# AliCampoPesca.net
KiCad netlist of a schematic drawn in EAGLE
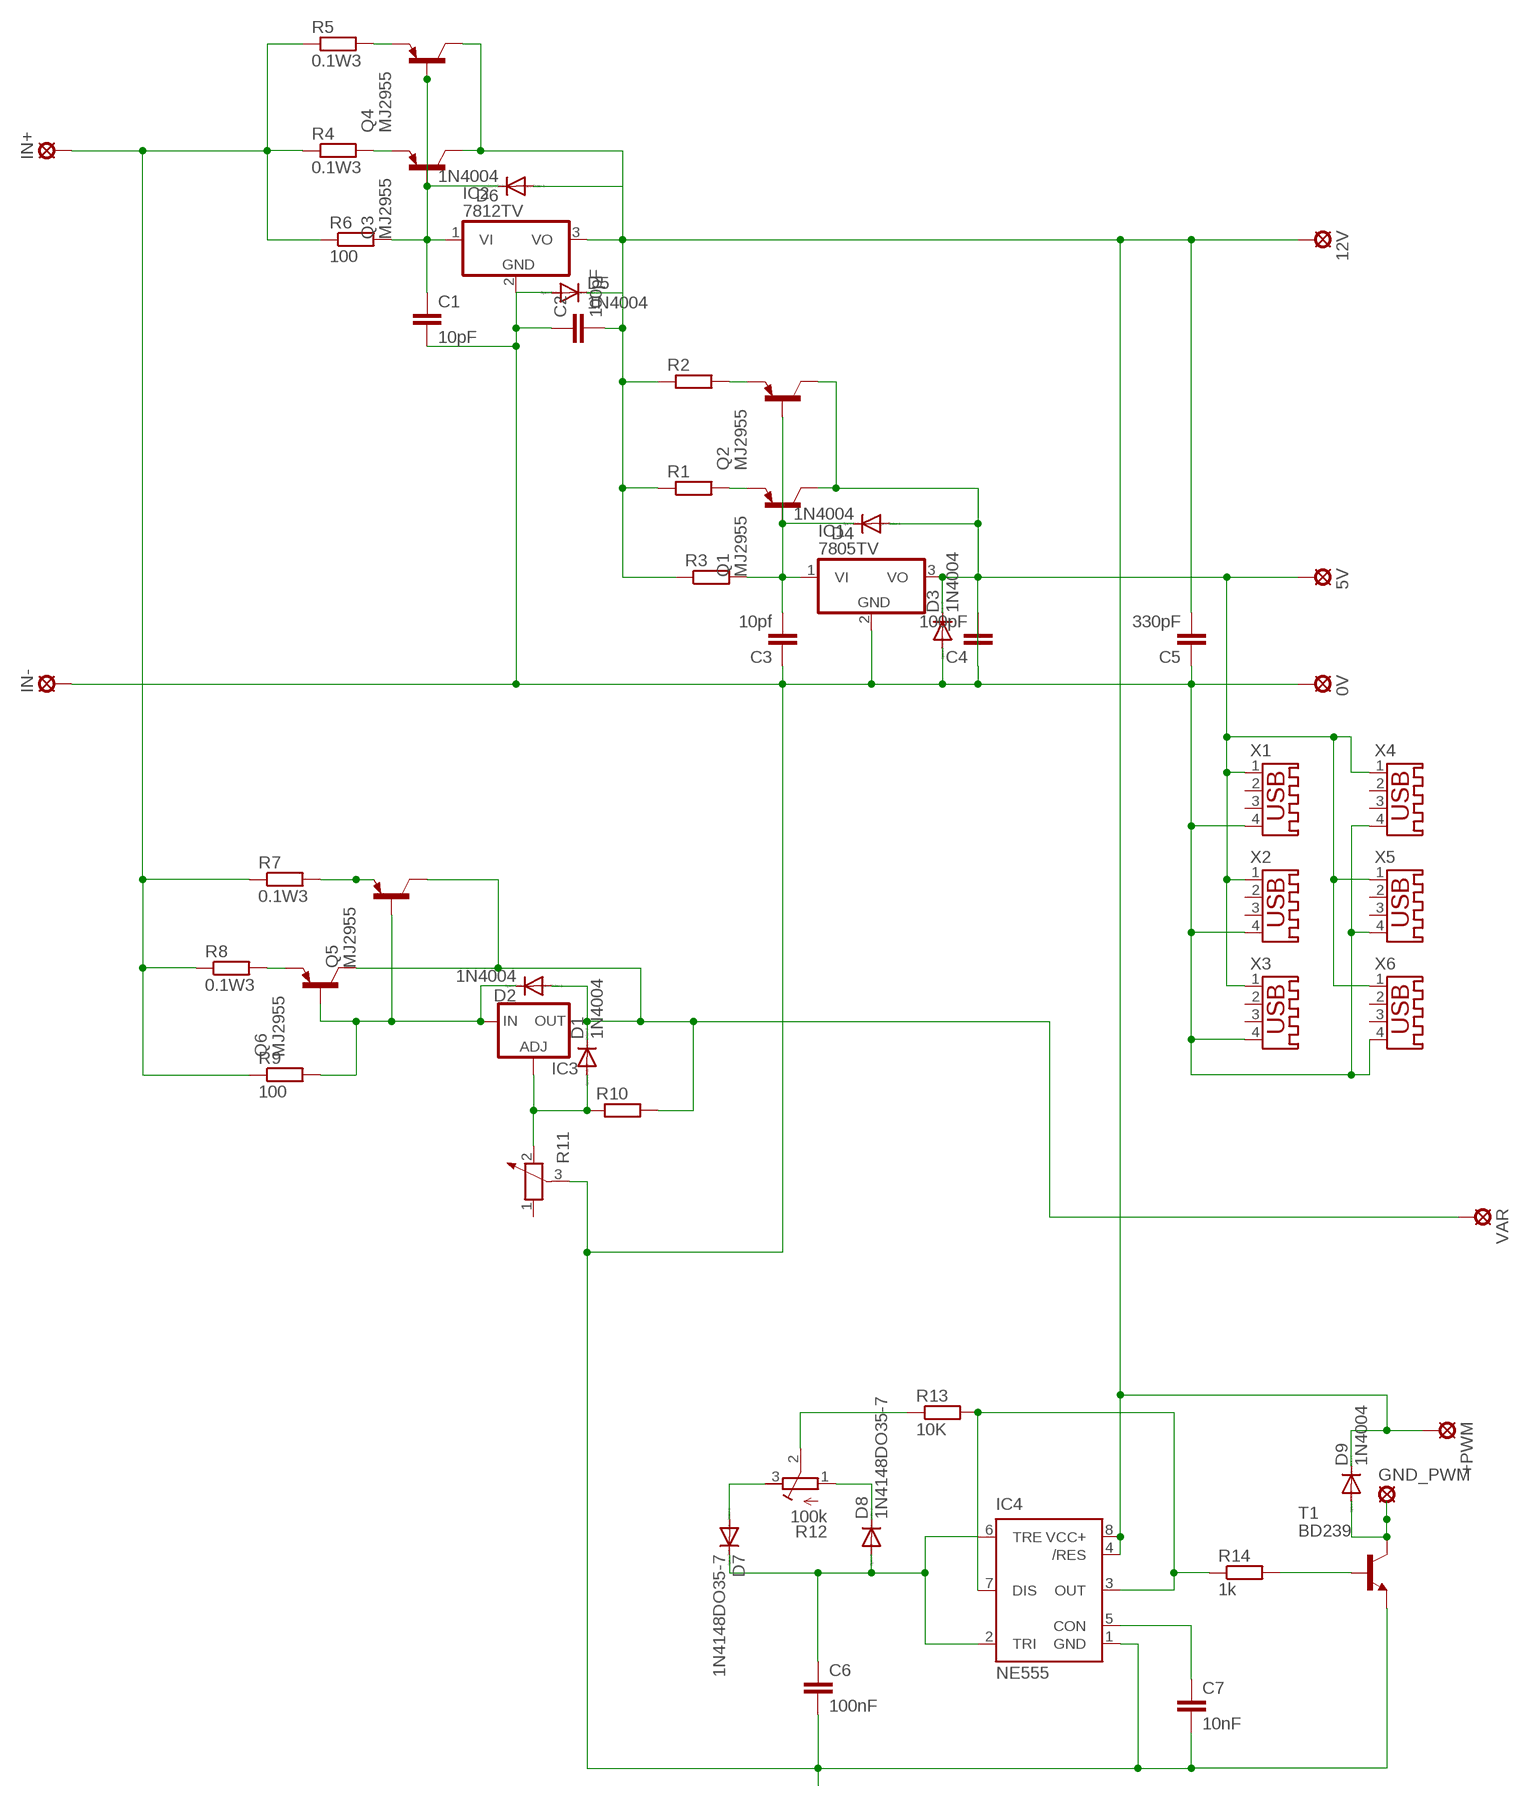
[diagram p0: schematic, sheet 1]

(export (version "E")
  (design (tool "Eeschema 10.0.6"))
  (components
    (comp (ref "+PWM")
      (value "LSP10")
      (footprint "eagle-import:LSP10")
      (libsource (lib "eagle-import") (part "LSP10"))
    )
    (comp (ref "0V")
      (value "SE14")
      (footprint "eagle-import:SE14")
      (libsource (lib "eagle-import") (part "SE14"))
    )
    (comp (ref "5V")
      (value "SE14")
      (footprint "eagle-import:SE14")
      (libsource (lib "eagle-import") (part "SE14"))
    )
    (comp (ref "12V")
      (value "SE14")
      (footprint "eagle-import:SE14")
      (libsource (lib "eagle-import") (part "SE14"))
    )
    (comp (ref "C1")
      (value "10pF")
      (footprint "eagle-import:C050-024X044")
      (libsource (lib "eagle-import") (part "C-EU050-024X044"))
    )
    (comp (ref "C2")
      (value "100pF")
      (footprint "eagle-import:C050-024X044")
      (libsource (lib "eagle-import") (part "C-EU050-024X044"))
    )
    (comp (ref "C3")
      (value "10pf")
      (footprint "eagle-import:C050-024X044")
      (libsource (lib "eagle-import") (part "C-EU050-024X044"))
    )
    (comp (ref "C4")
      (value "100pF")
      (footprint "eagle-import:C050-024X044")
      (libsource (lib "eagle-import") (part "C-EU050-024X044"))
    )
    (comp (ref "C5")
      (value "330pF")
      (footprint "eagle-import:C050-024X044")
      (libsource (lib "eagle-import") (part "C-EU050-024X044"))
    )
    (comp (ref "C6")
      (value "100nF")
      (footprint "eagle-import:C050-024X044")
      (libsource (lib "eagle-import") (part "C-EU050-024X044"))
    )
    (comp (ref "C7")
      (value "10nF")
      (footprint "eagle-import:C050-024X044")
      (libsource (lib "eagle-import") (part "C-EU050-024X044"))
    )
    (comp (ref "D1")
      (value "1N4004")
      (footprint "eagle-import:DO41-10")
      (libsource (lib "eagle-import") (part "1N4004"))
    )
    (comp (ref "D2")
      (value "1N4004")
      (footprint "eagle-import:DO41-10")
      (libsource (lib "eagle-import") (part "1N4004"))
    )
    (comp (ref "D3")
      (value "1N4004")
      (footprint "eagle-import:DO41-10")
      (libsource (lib "eagle-import") (part "1N4004"))
    )
    (comp (ref "D4")
      (value "1N4004")
      (footprint "eagle-import:DO41-10")
      (libsource (lib "eagle-import") (part "1N4004"))
    )
    (comp (ref "D5")
      (value "1N4004")
      (footprint "eagle-import:DO41-10")
      (libsource (lib "eagle-import") (part "1N4004"))
    )
    (comp (ref "D6")
      (value "1N4004")
      (footprint "eagle-import:DO41-10")
      (libsource (lib "eagle-import") (part "1N4004"))
    )
    (comp (ref "D7")
      (value "1N4148DO35-7")
      (footprint "eagle-import:DO35-7")
      (libsource (lib "eagle-import") (part "1N4148DO35-7"))
    )
    (comp (ref "D8")
      (value "1N4148DO35-7")
      (footprint "eagle-import:DO35-7")
      (libsource (lib "eagle-import") (part "1N4148DO35-7"))
    )
    (comp (ref "D9")
      (value "1N4004")
      (footprint "eagle-import:DO41-10")
      (libsource (lib "eagle-import") (part "1N4004"))
    )
    (comp (ref "GND_PWM")
      (value "LSP10")
      (footprint "eagle-import:LSP10")
      (libsource (lib "eagle-import") (part "LSP10"))
    )
    (comp (ref "IC1")
      (value "7805TV")
      (footprint "eagle-import:TO220V")
      (libsource (lib "eagle-import") (part "78TV05"))
    )
    (comp (ref "IC2")
      (value "7812TV")
      (footprint "eagle-import:TO220V")
      (libsource (lib "eagle-import") (part "78TV12"))
    )
    (comp (ref "IC3")
      (value "LM317TS")
      (footprint "eagle-import:317TS")
      (libsource (lib "eagle-import") (part "LM317TS"))
    )
    (comp (ref "IC4")
      (value "NE555")
      (footprint "eagle-import:DIL-08")
      (fields (field (name "MF") "Arrow Electronics") (field (name "MPN") "NE555N"))
      (libsource (lib "eagle-import") (part "NE555"))
    )
    (comp (ref "IN+")
      (value "SE14")
      (footprint "eagle-import:SE14")
      (libsource (lib "eagle-import") (part "SE14"))
    )
    (comp (ref "IN-")
      (value "SE14")
      (footprint "eagle-import:SE14")
      (libsource (lib "eagle-import") (part "SE14"))
    )
    (comp (ref "Q1")
      (value "MJ2955")
      (footprint "eagle-import:TO3")
      (libsource (lib "eagle-import") (part "MJ2955"))
    )
    (comp (ref "Q2")
      (value "MJ2955")
      (footprint "eagle-import:TO3")
      (libsource (lib "eagle-import") (part "MJ2955"))
    )
    (comp (ref "Q3")
      (value "MJ2955")
      (footprint "eagle-import:TO3")
      (libsource (lib "eagle-import") (part "MJ2955"))
    )
    (comp (ref "Q4")
      (value "MJ2955")
      (footprint "eagle-import:TO3")
      (libsource (lib "eagle-import") (part "MJ2955"))
    )
    (comp (ref "Q5")
      (value "MJ2955")
      (footprint "eagle-import:TO3")
      (libsource (lib "eagle-import") (part "MJ2955"))
    )
    (comp (ref "Q6")
      (value "MJ2955")
      (footprint "eagle-import:TO3")
      (libsource (lib "eagle-import") (part "MJ2955"))
    )
    (comp (ref "R1")
      (value "R-EU_0207/15")
      (footprint "eagle-import:0207_15")
      (libsource (lib "eagle-import") (part "R-EU_0207/15"))
    )
    (comp (ref "R2")
      (value "R-EU_0207/15")
      (footprint "eagle-import:0207_15")
      (libsource (lib "eagle-import") (part "R-EU_0207/15"))
    )
    (comp (ref "R3")
      (value "R-EU_0207/15")
      (footprint "eagle-import:0207_15")
      (libsource (lib "eagle-import") (part "R-EU_0207/15"))
    )
    (comp (ref "R4")
      (value "0.1W3")
      (footprint "eagle-import:0207_15")
      (libsource (lib "eagle-import") (part "R-EU_0207/15"))
    )
    (comp (ref "R5")
      (value "0.1W3")
      (footprint "eagle-import:0207_15")
      (libsource (lib "eagle-import") (part "R-EU_0207/15"))
    )
    (comp (ref "R6")
      (value "100")
      (footprint "eagle-import:0207_15")
      (libsource (lib "eagle-import") (part "R-EU_0207/15"))
    )
    (comp (ref "R7")
      (value "0.1W3")
      (footprint "eagle-import:0207_15")
      (libsource (lib "eagle-import") (part "R-EU_0207/15"))
    )
    (comp (ref "R8")
      (value "0.1W3")
      (footprint "eagle-import:0207_15")
      (libsource (lib "eagle-import") (part "R-EU_0207/15"))
    )
    (comp (ref "R9")
      (value "100")
      (footprint "eagle-import:0207_15")
      (libsource (lib "eagle-import") (part "R-EU_0207/15"))
    )
    (comp (ref "R10")
      (value "R-EU_0207/12")
      (footprint "eagle-import:0207_12")
      (libsource (lib "eagle-import") (part "R-EU_0207/12"))
    )
    (comp (ref "R11")
      (value "POTENTIOMETER_PT-10")
      (footprint "eagle-import:PT-10")
      (libsource (lib "eagle-import") (part "POTENTIOMETER_PT-10"))
    )
    (comp (ref "R12")
      (value "100k")
      (footprint "eagle-import:RTRIM3339P")
      (libsource (lib "eagle-import") (part "R-TRIMM3339P"))
    )
    (comp (ref "R13")
      (value "10K")
      (footprint "eagle-import:0204_7")
      (libsource (lib "eagle-import") (part "R-EU_0204/7"))
    )
    (comp (ref "R14")
      (value "1k")
      (footprint "eagle-import:0207_10")
      (libsource (lib "eagle-import") (part "R-EU_0207/10"))
    )
    (comp (ref "T1")
      (value "BD239")
      (footprint "eagle-import:TO220")
      (libsource (lib "eagle-import") (part "BD239"))
    )
    (comp (ref "VAR")
      (value "SE14")
      (footprint "eagle-import:SE14")
      (libsource (lib "eagle-import") (part "SE14"))
    )
    (comp (ref "X1")
      (value "USB-A003")
      (footprint "eagle-import:USB-A003")
      (libsource (lib "eagle-import") (part "USB-A003"))
    )
    (comp (ref "X2")
      (value "USB-A003")
      (footprint "eagle-import:USB-A003")
      (libsource (lib "eagle-import") (part "USB-A003"))
    )
    (comp (ref "X3")
      (value "USB-A003")
      (footprint "eagle-import:USB-A003")
      (libsource (lib "eagle-import") (part "USB-A003"))
    )
    (comp (ref "X4")
      (value "USB-A003")
      (footprint "eagle-import:USB-A003")
      (libsource (lib "eagle-import") (part "USB-A003"))
    )
    (comp (ref "X5")
      (value "USB-A003")
      (footprint "eagle-import:USB-A003")
      (libsource (lib "eagle-import") (part "USB-A003"))
    )
    (comp (ref "X6")
      (value "USB-A003")
      (footprint "eagle-import:USB-A003")
      (libsource (lib "eagle-import") (part "USB-A003"))
    )
  )
  (nets
    (net (code "1") (name "Net-(IC1-GND)") (class "Default")
      (node (ref "0V") (pin "MP") (pinfunction "MP_MP") (pintype "passive"))
      (node (ref "5V") (pin "MP") (pinfunction "MP_MP") (pintype "passive"))
      (node (ref "C1") (pin "2") (pinfunction "2_2") (pintype "passive"))
      (node (ref "C2") (pin "1") (pinfunction "1_1") (pintype "passive"))
      (node (ref "C3") (pin "1") (pinfunction "1_1") (pintype "passive"))
      (node (ref "C4") (pin "1") (pinfunction "1_1") (pintype "passive"))
      (node (ref "C4") (pin "2") (pinfunction "2_2") (pintype "passive"))
      (node (ref "C5") (pin "1") (pinfunction "1_1") (pintype "passive"))
      (node (ref "C6") (pin "2") (pinfunction "2_2") (pintype "passive"))
      (node (ref "C7") (pin "2") (pinfunction "2_2") (pintype "passive"))
      (node (ref "D3") (pin "A") (pinfunction "A_A") (pintype "passive"))
      (node (ref "D3") (pin "C") (pinfunction "C_C") (pintype "passive"))
      (node (ref "D4") (pin "A") (pinfunction "A_A") (pintype "passive"))
      (node (ref "D5") (pin "A") (pinfunction "A_A") (pintype "passive"))
      (node (ref "IC1") (pin "2") (pinfunction "GND_2") (pintype "passive"))
      (node (ref "IC1") (pin "3") (pinfunction "VO_3") (pintype "passive"))
      (node (ref "IC2") (pin "2") (pinfunction "GND_2") (pintype "passive"))
      (node (ref "IC4") (pin "1") (pinfunction "GND_1") (pintype "power_in"))
      (node (ref "IN-") (pin "MP") (pinfunction "MP_MP") (pintype "passive"))
      (node (ref "Q1") (pin "C") (pinfunction "C_C") (pintype "passive"))
      (node (ref "Q1") (pin "C/") (pinfunction "C_C/") (pintype "passive"))
      (node (ref "Q2") (pin "C") (pinfunction "C_C") (pintype "passive"))
      (node (ref "Q2") (pin "C/") (pinfunction "C_C/") (pintype "passive"))
      (node (ref "R11") (pin "3") (pinfunction "3_3") (pintype "passive"))
      (node (ref "T1") (pin "3") (pinfunction "E_3") (pintype "passive"))
      (node (ref "X1") (pin "1") (pinfunction "1_1") (pintype "passive"))
      (node (ref "X1") (pin "4") (pinfunction "4_4") (pintype "passive"))
      (node (ref "X2") (pin "1") (pinfunction "1_1") (pintype "passive"))
      (node (ref "X2") (pin "4") (pinfunction "4_4") (pintype "passive"))
      (node (ref "X3") (pin "1") (pinfunction "1_1") (pintype "passive"))
      (node (ref "X3") (pin "4") (pinfunction "4_4") (pintype "passive"))
      (node (ref "X4") (pin "1") (pinfunction "1_1") (pintype "passive"))
      (node (ref "X4") (pin "4") (pinfunction "4_4") (pintype "passive"))
      (node (ref "X5") (pin "1") (pinfunction "1_1") (pintype "passive"))
      (node (ref "X5") (pin "4") (pinfunction "4_4") (pintype "passive"))
      (node (ref "X6") (pin "1") (pinfunction "1_1") (pintype "passive"))
      (node (ref "X6") (pin "4") (pinfunction "4_4") (pintype "passive"))
    )
    (net (code "2") (name "Net-(IC1-VI)") (class "Default")
      (node (ref "C3") (pin "2") (pinfunction "2_2") (pintype "passive"))
      (node (ref "D4") (pin "C") (pinfunction "C_C") (pintype "passive"))
      (node (ref "IC1") (pin "1") (pinfunction "VI_1") (pintype "input"))
      (node (ref "Q1") (pin "B") (pinfunction "B_B") (pintype "passive"))
      (node (ref "Q2") (pin "B") (pinfunction "B_B") (pintype "passive"))
      (node (ref "R3") (pin "2") (pinfunction "2_2") (pintype "passive"))
    )
    (net (code "3") (name "Net-(IC2-VI)") (class "Default")
      (node (ref "C1") (pin "1") (pinfunction "1_1") (pintype "passive"))
      (node (ref "D6") (pin "C") (pinfunction "C_C") (pintype "passive"))
      (node (ref "IC2") (pin "1") (pinfunction "VI_1") (pintype "input"))
      (node (ref "Q3") (pin "B") (pinfunction "B_B") (pintype "passive"))
      (node (ref "Q4") (pin "B") (pinfunction "B_B") (pintype "passive"))
      (node (ref "R6") (pin "2") (pinfunction "2_2") (pintype "passive"))
    )
    (net (code "4") (name "Net-(IC2-VO)") (class "Default")
      (node (ref "+PWM") (pin "MP") (pinfunction "MP_MP") (pintype "passive"))
      (node (ref "12V") (pin "MP") (pinfunction "MP_MP") (pintype "passive"))
      (node (ref "C2") (pin "2") (pinfunction "2_2") (pintype "passive"))
      (node (ref "C5") (pin "2") (pinfunction "2_2") (pintype "passive"))
      (node (ref "D5") (pin "C") (pinfunction "C_C") (pintype "passive"))
      (node (ref "D6") (pin "A") (pinfunction "A_A") (pintype "passive"))
      (node (ref "D9") (pin "C") (pinfunction "C_C") (pintype "passive"))
      (node (ref "IC2") (pin "3") (pinfunction "VO_3") (pintype "passive"))
      (node (ref "IC4") (pin "4") (pinfunction "/RES_4") (pintype "input"))
      (node (ref "IC4") (pin "8") (pinfunction "VCC+_8") (pintype "power_in"))
      (node (ref "Q3") (pin "C") (pinfunction "C_C") (pintype "passive"))
      (node (ref "Q3") (pin "C/") (pinfunction "C_C/") (pintype "passive"))
      (node (ref "Q4") (pin "C") (pinfunction "C_C") (pintype "passive"))
      (node (ref "Q4") (pin "C/") (pinfunction "C_C/") (pintype "passive"))
      (node (ref "R1") (pin "1") (pinfunction "1_1") (pintype "passive"))
      (node (ref "R2") (pin "1") (pinfunction "1_1") (pintype "passive"))
      (node (ref "R3") (pin "1") (pinfunction "1_1") (pintype "passive"))
    )
    (net (code "5") (name "Net-(IC3-ADJ)") (class "Default")
      (node (ref "D1") (pin "A") (pinfunction "A_A") (pintype "passive"))
      (node (ref "IC3") (pin "1") (pinfunction "ADJ_1") (pintype "input"))
      (node (ref "R10") (pin "1") (pinfunction "1_1") (pintype "passive"))
      (node (ref "R11") (pin "2") (pinfunction "2_2") (pintype "passive"))
    )
    (net (code "6") (name "Net-(IC3-IN)") (class "Default")
      (node (ref "D2") (pin "C") (pinfunction "C_C") (pintype "passive"))
      (node (ref "IC3") (pin "3") (pinfunction "IN_3") (pintype "input"))
      (node (ref "Q5") (pin "B") (pinfunction "B_B") (pintype "passive"))
      (node (ref "Q6") (pin "B") (pinfunction "B_B") (pintype "passive"))
      (node (ref "R9") (pin "2") (pinfunction "2_2") (pintype "passive"))
    )
    (net (code "7") (name "Net-(IC3-OUT)") (class "Default")
      (node (ref "D1") (pin "C") (pinfunction "C_C") (pintype "passive"))
      (node (ref "D2") (pin "A") (pinfunction "A_A") (pintype "passive"))
      (node (ref "IC3") (pin "2") (pinfunction "OUT_2") (pintype "passive"))
      (node (ref "Q5") (pin "C") (pinfunction "C_C") (pintype "passive"))
      (node (ref "Q5") (pin "C/") (pinfunction "C_C/") (pintype "passive"))
      (node (ref "Q6") (pin "C") (pinfunction "C_C") (pintype "passive"))
      (node (ref "Q6") (pin "C/") (pinfunction "C_C/") (pintype "passive"))
      (node (ref "R10") (pin "2") (pinfunction "2_2") (pintype "passive"))
      (node (ref "VAR") (pin "MP") (pinfunction "MP_MP") (pintype "passive"))
    )
    (net (code "8") (name "Net-(IC4-CON)") (class "Default")
      (node (ref "C7") (pin "1") (pinfunction "1_1") (pintype "passive"))
      (node (ref "IC4") (pin "5") (pinfunction "CON_5") (pintype "input"))
    )
    (net (code "9") (name "Net-(IC4-DIS)") (class "Default")
      (node (ref "IC4") (pin "3") (pinfunction "OUT_3") (pintype "output"))
      (node (ref "IC4") (pin "7") (pinfunction "DIS_7") (pintype "input"))
      (node (ref "R13") (pin "2") (pinfunction "2_2") (pintype "passive"))
      (node (ref "R14") (pin "1") (pinfunction "1_1") (pintype "passive"))
    )
    (net (code "10") (name "Net-(IC4-TRE)") (class "Default")
      (node (ref "C6") (pin "1") (pinfunction "1_1") (pintype "passive"))
      (node (ref "D7") (pin "C") (pinfunction "C_C") (pintype "passive"))
      (node (ref "D8") (pin "A") (pinfunction "A_A") (pintype "passive"))
      (node (ref "IC4") (pin "2") (pinfunction "TRI_2") (pintype "input"))
      (node (ref "IC4") (pin "6") (pinfunction "TRE_6") (pintype "input"))
    )
    (net (code "11") (name "Net-(IN+-PadMP)") (class "Default")
      (node (ref "IN+") (pin "MP") (pinfunction "MP_MP") (pintype "passive"))
      (node (ref "R4") (pin "1") (pinfunction "1_1") (pintype "passive"))
      (node (ref "R5") (pin "1") (pinfunction "1_1") (pintype "passive"))
      (node (ref "R6") (pin "1") (pinfunction "1_1") (pintype "passive"))
      (node (ref "R7") (pin "1") (pinfunction "1_1") (pintype "passive"))
      (node (ref "R8") (pin "1") (pinfunction "1_1") (pintype "passive"))
      (node (ref "R9") (pin "1") (pinfunction "1_1") (pintype "passive"))
    )
    (net (code "12") (name "Net-(Q1-PadE)") (class "Default")
      (node (ref "Q1") (pin "E") (pinfunction "E_E") (pintype "passive"))
      (node (ref "R1") (pin "2") (pinfunction "2_2") (pintype "passive"))
    )
    (net (code "13") (name "Net-(Q2-PadE)") (class "Default")
      (node (ref "Q2") (pin "E") (pinfunction "E_E") (pintype "passive"))
      (node (ref "R2") (pin "2") (pinfunction "2_2") (pintype "passive"))
    )
    (net (code "14") (name "Net-(Q3-PadE)") (class "Default")
      (node (ref "Q3") (pin "E") (pinfunction "E_E") (pintype "passive"))
      (node (ref "R4") (pin "2") (pinfunction "2_2") (pintype "passive"))
    )
    (net (code "15") (name "Net-(Q4-PadE)") (class "Default")
      (node (ref "Q4") (pin "E") (pinfunction "E_E") (pintype "passive"))
      (node (ref "R5") (pin "2") (pinfunction "2_2") (pintype "passive"))
    )
    (net (code "16") (name "Net-(Q5-PadE)") (class "Default")
      (node (ref "Q5") (pin "E") (pinfunction "E_E") (pintype "passive"))
      (node (ref "R7") (pin "2") (pinfunction "2_2") (pintype "passive"))
    )
    (net (code "17") (name "Net-(Q6-PadE)") (class "Default")
      (node (ref "Q6") (pin "E") (pinfunction "E_E") (pintype "passive"))
      (node (ref "R8") (pin "2") (pinfunction "2_2") (pintype "passive"))
    )
    (net (code "18") (name "Net-(R12-A)") (class "Default")
      (node (ref "D8") (pin "C") (pinfunction "C_C") (pintype "passive"))
      (node (ref "R12") (pin "1") (pinfunction "A_1") (pintype "passive"))
    )
    (net (code "19") (name "Net-(R12-E)") (class "Default")
      (node (ref "D7") (pin "A") (pinfunction "A_A") (pintype "passive"))
      (node (ref "R12") (pin "3") (pinfunction "E_3") (pintype "passive"))
    )
    (net (code "20") (name "Net-(R12-S)") (class "Default")
      (node (ref "R12") (pin "2") (pinfunction "S_2") (pintype "passive"))
      (node (ref "R13") (pin "1") (pinfunction "1_1") (pintype "passive"))
    )
    (net (code "21") (name "Net-(T1-B)") (class "Default")
      (node (ref "R14") (pin "2") (pinfunction "2_2") (pintype "passive"))
      (node (ref "T1") (pin "1") (pinfunction "B_1") (pintype "passive"))
    )
    (net (code "22") (name "Net-(T1-C)") (class "Default")
      (node (ref "D9") (pin "A") (pinfunction "A_A") (pintype "passive"))
      (node (ref "GND_PWM") (pin "MP") (pinfunction "MP_MP") (pintype "passive"))
      (node (ref "T1") (pin "2") (pinfunction "C_2") (pintype "passive"))
    )
    (net (code "23") (name "unconnected-(R11-Pad1)") (class "Default")
      (node (ref "R11") (pin "1") (pinfunction "1_1") (pintype "passive"))
    )
    (net (code "24") (name "unconnected-(X1-Pad2)") (class "Default")
      (node (ref "X1") (pin "2") (pinfunction "2_2") (pintype "passive"))
    )
    (net (code "25") (name "unconnected-(X1-Pad3)") (class "Default")
      (node (ref "X1") (pin "3") (pinfunction "3_3") (pintype "passive"))
    )
    (net (code "26") (name "unconnected-(X2-Pad2)") (class "Default")
      (node (ref "X2") (pin "2") (pinfunction "2_2") (pintype "passive"))
    )
    (net (code "27") (name "unconnected-(X2-Pad3)") (class "Default")
      (node (ref "X2") (pin "3") (pinfunction "3_3") (pintype "passive"))
    )
    (net (code "28") (name "unconnected-(X3-Pad2)") (class "Default")
      (node (ref "X3") (pin "2") (pinfunction "2_2") (pintype "passive"))
    )
    (net (code "29") (name "unconnected-(X3-Pad3)") (class "Default")
      (node (ref "X3") (pin "3") (pinfunction "3_3") (pintype "passive"))
    )
    (net (code "30") (name "unconnected-(X4-Pad2)") (class "Default")
      (node (ref "X4") (pin "2") (pinfunction "2_2") (pintype "passive"))
    )
    (net (code "31") (name "unconnected-(X4-Pad3)") (class "Default")
      (node (ref "X4") (pin "3") (pinfunction "3_3") (pintype "passive"))
    )
    (net (code "32") (name "unconnected-(X5-Pad2)") (class "Default")
      (node (ref "X5") (pin "2") (pinfunction "2_2") (pintype "passive"))
    )
    (net (code "33") (name "unconnected-(X5-Pad3)") (class "Default")
      (node (ref "X5") (pin "3") (pinfunction "3_3") (pintype "passive"))
    )
    (net (code "34") (name "unconnected-(X6-Pad2)") (class "Default")
      (node (ref "X6") (pin "2") (pinfunction "2_2") (pintype "passive"))
    )
    (net (code "35") (name "unconnected-(X6-Pad3)") (class "Default")
      (node (ref "X6") (pin "3") (pinfunction "3_3") (pintype "passive"))
    )
  )
)
